# eMMC_FLASH.net
KiCad netlist of a schematic drawn in Altium Designer
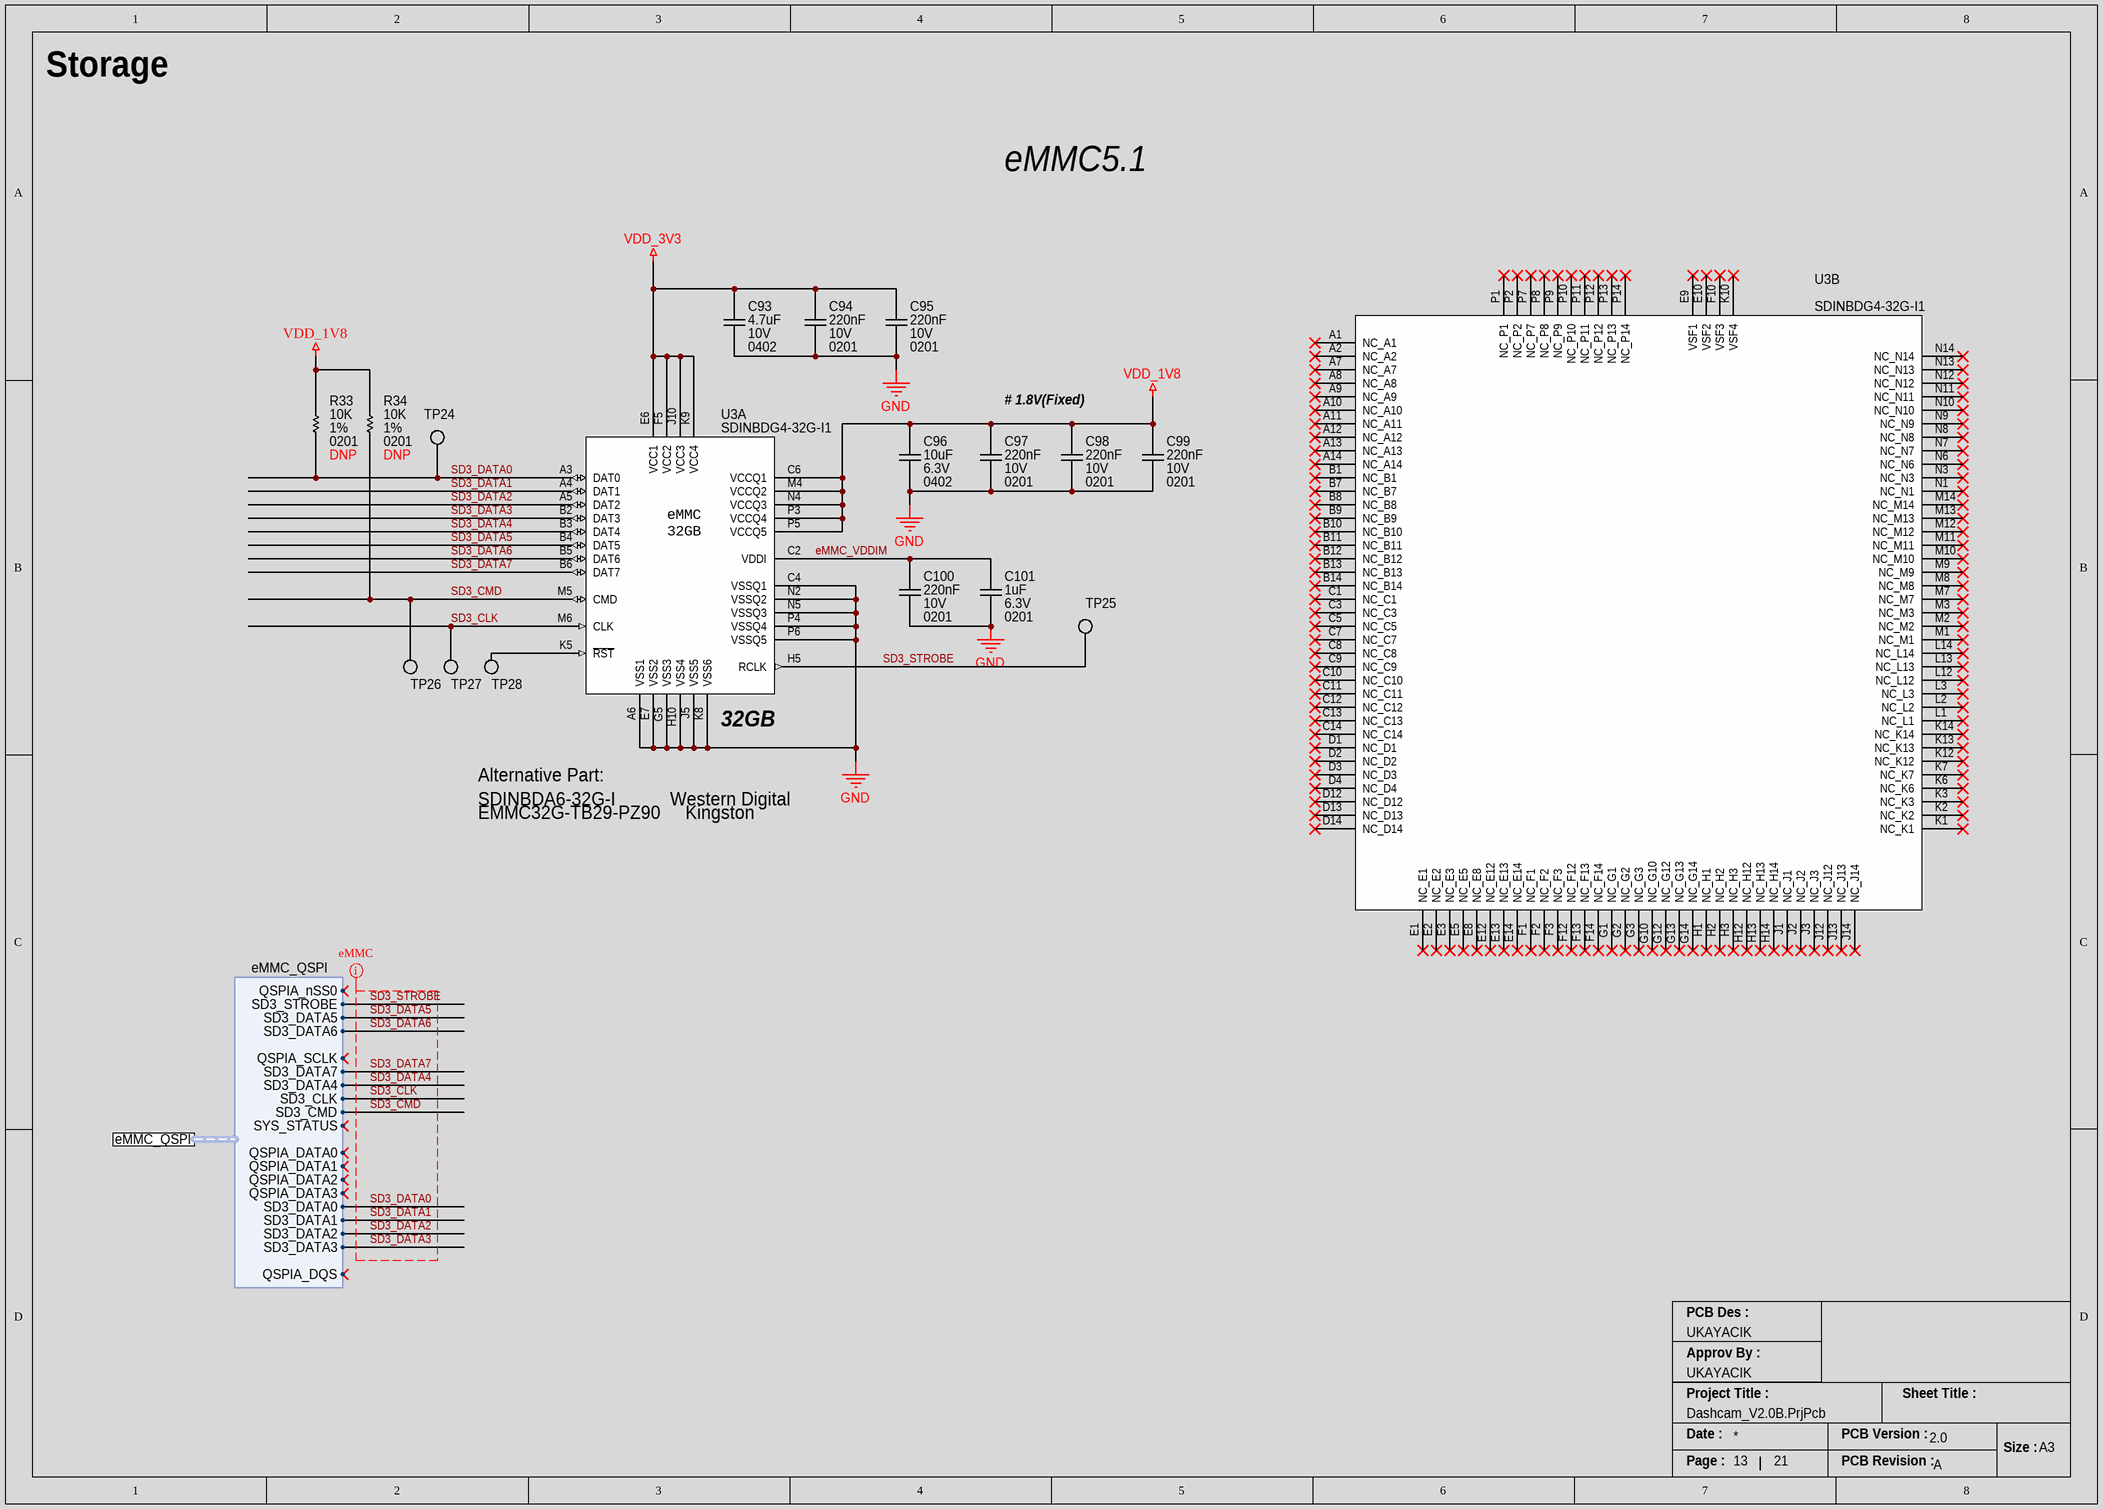
[diagram p0: eMMC FLASH.SchDoc]

(export (version "E")
  (design (tool "Eeschema 10.0.6"))
  (components
    (comp (ref "C93")
      (value "CL05A475KP5NRNC")
      (footprint "CAP_0402_CAPC1005X05N")
      (description "Multilayer Ceramic Capacitor, 4.7 uF, 10 V, ± 10%, X5R, 0402 [1005 Metric]")
      (fields
        (field (name "MANUFACTURER") "Samsung")
        (field (name "TOLERANCE") "10%")
        (field (name "CAPACITANCE") "4.7uF")
        (field (name "VOLTAGE RATING") "10V")
        (field (name "CASE/PACKAGE") "0402")
      )
      (libsource (lib "Electronic Devices_LIB") (part "CAP_4.7UF_10V_X5R_0402"))
    )
    (comp (ref "C94")
      (value "LMK063BJ224MP-F")
      (footprint "CAP_0201_CAPC0603X03N")
      (description "Multilayer Ceramic Capacitors (High dielectric type), 10V, 0.22 uF, ± 20 %, 0201, X5R, RoHS")
      (fields
        (field (name "MANUFACTURER") "Taiyo Yuden")
        (field (name "TOLERANCE") "20%")
        (field (name "VOLTAGE RATING (DC)") "10V")
        (field (name "CAPACITANCE") "220nF")
        (field (name "CASE/PACKAGE") "0201")
      )
      (libsource (lib "Electronic Devices_LIB") (part "CAP_0.22UF_10V_X5R_0201"))
    )
    (comp (ref "C95")
      (value "LMK063BJ224MP-F")
      (footprint "CAP_0201_CAPC0603X03N")
      (description "Multilayer Ceramic Capacitors (High dielectric type), 10V, 0.22 uF, ± 20 %, 0201, X5R, RoHS")
      (fields
        (field (name "MANUFACTURER") "Taiyo Yuden")
        (field (name "TOLERANCE") "20%")
        (field (name "VOLTAGE RATING (DC)") "10V")
        (field (name "CAPACITANCE") "220nF")
        (field (name "CASE/PACKAGE") "0201")
      )
      (libsource (lib "Electronic Devices_LIB") (part "CAP_0.22UF_10V_X5R_0201"))
    )
    (comp (ref "C96")
      (value "CL05A106MQ5NUNC")
      (footprint "CAP_0402_CAPC1005X05N")
      (description "Cap Ceramic 10uF 6.3V X5R 20% SMD 0402 85C T/R")
      (fields
        (field (name "MANUFACTURER") "Samsung")
        (field (name "TOLERANCE") "20%")
        (field (name "CASE/PACKAGE") "0402")
        (field (name "CAPACITANCE") "10uF")
        (field (name "VOLTAGE RATING") "6.3V")
      )
      (libsource (lib "Electronic Devices_LIB") (part "CAP_10UF_6.3V_X5R_0402"))
    )
    (comp (ref "C97")
      (value "LMK063BJ224MP-F")
      (footprint "CAP_0201_CAPC0603X03N")
      (description "Multilayer Ceramic Capacitors (High dielectric type), 10V, 0.22 uF, ± 20 %, 0201, X5R, RoHS")
      (fields
        (field (name "MANUFACTURER") "Taiyo Yuden")
        (field (name "TOLERANCE") "20%")
        (field (name "VOLTAGE RATING (DC)") "10V")
        (field (name "CAPACITANCE") "220nF")
        (field (name "CASE/PACKAGE") "0201")
      )
      (libsource (lib "Electronic Devices_LIB") (part "CAP_0.22UF_10V_X5R_0201"))
    )
    (comp (ref "C98")
      (value "LMK063BJ224MP-F")
      (footprint "CAP_0201_CAPC0603X03N")
      (description "Multilayer Ceramic Capacitors (High dielectric type), 10V, 0.22 uF, ± 20 %, 0201, X5R, RoHS")
      (fields
        (field (name "MANUFACTURER") "Taiyo Yuden")
        (field (name "TOLERANCE") "20%")
        (field (name "VOLTAGE RATING (DC)") "10V")
        (field (name "CAPACITANCE") "220nF")
        (field (name "CASE/PACKAGE") "0201")
      )
      (libsource (lib "Electronic Devices_LIB") (part "CAP_0.22UF_10V_X5R_0201"))
    )
    (comp (ref "C99")
      (value "LMK063BJ224MP-F")
      (footprint "CAP_0201_CAPC0603X03N")
      (description "Multilayer Ceramic Capacitors (High dielectric type), 10V, 0.22 uF, ± 20 %, 0201, X5R, RoHS")
      (fields
        (field (name "MANUFACTURER") "Taiyo Yuden")
        (field (name "TOLERANCE") "20%")
        (field (name "VOLTAGE RATING (DC)") "10V")
        (field (name "CAPACITANCE") "220nF")
        (field (name "CASE/PACKAGE") "0201")
      )
      (libsource (lib "Electronic Devices_LIB") (part "CAP_0.22UF_10V_X5R_0201"))
    )
    (comp (ref "C100")
      (value "LMK063BJ224MP-F")
      (footprint "CAP_0201_CAPC0603X03N")
      (description "Multilayer Ceramic Capacitors (High dielectric type), 10V, 0.22 uF, ± 20 %, 0201, X5R, RoHS")
      (fields
        (field (name "MANUFACTURER") "Taiyo Yuden")
        (field (name "TOLERANCE") "20%")
        (field (name "VOLTAGE RATING (DC)") "10V")
        (field (name "CAPACITANCE") "220nF")
        (field (name "CASE/PACKAGE") "0201")
      )
      (libsource (lib "Electronic Devices_LIB") (part "CAP_0.22UF_10V_X5R_0201"))
    )
    (comp (ref "C101")
      (value "02016D105MAT2A")
      (footprint "CAP_0201_CAPC0603X03N")
      (description "0201 1 uF 6.3 V ±20 % Tolerance X5R Surface Mount Multilayer Ceramic Capacitor")
      (fields
        (field (name "MANUFACTURER") "Kyocera AVX")
        (field (name "TOLERANCE") "20%")
        (field (name "VOLTAGE RATING (DC)") "6.3V")
        (field (name "CAPACITANCE") "1uF")
        (field (name "CASE/PACKAGE") "0201")
      )
      (libsource (lib "Electronic Devices_LIB") (part "CAP_1UF_6.3V_X5R_0201"))
    )
    (comp (ref "R33")
      (value "RC0201FR-0710KL")
      (footprint "RES_0201_RESC0603X02N")
      (description "SMD Chip Resistor, 10 kOhm, ± 1%, 50 mW, 0201 [0603 Metric], Thick Film, General Purpose")
      (fields
        (field (name "MANUFACTURER") "Yageo")
        (field (name "TOLERANCE") "1%")
        (field (name "RESISTANCE") "10K")
        (field (name "CASE CODE (IMPERIAL)") "0201")
      )
      (libsource (lib "Electronic Devices_LIB") (part "RES_10K_1/12W_1%_0201"))
    )
    (comp (ref "R34")
      (value "RC0201FR-0710KL")
      (footprint "RES_0201_RESC0603X02N")
      (description "SMD Chip Resistor, 10 kOhm, ± 1%, 50 mW, 0201 [0603 Metric], Thick Film, General Purpose")
      (fields
        (field (name "MANUFACTURER") "Yageo")
        (field (name "TOLERANCE") "1%")
        (field (name "RESISTANCE") "10K")
        (field (name "CASE CODE (IMPERIAL)") "0201")
      )
      (libsource (lib "Electronic Devices_LIB") (part "RES_10K_1/12W_1%_0201"))
    )
    (comp (ref "TP24")
      (value "NO COMPONENT")
      (footprint "TP_PAD_0.5MM_SMD_ROUND")
      (description "Test Point, SMD pad, round, 1.5mm, 1.6mm, 3mm diameter")
      (libsource (lib "Electronic Devices_LIB") (part "TP_PAD_SMD_SMALL"))
    )
    (comp (ref "TP25")
      (value "NO COMPONENT")
      (footprint "TP_PAD_0.5MM_SMD_ROUND")
      (description "Test Point, SMD pad, round, 1.5mm, 1.6mm, 3mm diameter")
      (libsource (lib "Electronic Devices_LIB") (part "TP_PAD_SMD_SMALL"))
    )
    (comp (ref "TP26")
      (value "NO COMPONENT")
      (footprint "TP_PAD_0.5MM_SMD_ROUND")
      (description "Test Point, SMD pad, round, 1.5mm, 1.6mm, 3mm diameter")
      (libsource (lib "Electronic Devices_LIB") (part "TP_PAD_SMD_SMALL"))
    )
    (comp (ref "TP27")
      (value "NO COMPONENT")
      (footprint "TP_PAD_0.5MM_SMD_ROUND")
      (description "Test Point, SMD pad, round, 1.5mm, 1.6mm, 3mm diameter")
      (libsource (lib "Electronic Devices_LIB") (part "TP_PAD_SMD_SMALL"))
    )
    (comp (ref "TP28")
      (value "NO COMPONENT")
      (footprint "TP_PAD_0.5MM_SMD_ROUND")
      (description "Test Point, SMD pad, round, 1.5mm, 1.6mm, 3mm diameter")
      (libsource (lib "Electronic Devices_LIB") (part "TP_PAD_SMD_SMALL"))
    )
    (comp (ref "U3")
      (value "SDINBDG4-32G-I1")
      (footprint "IC_MEMORY_eMMC")
      (description "Inand 7250 32GB Industrial Wide Temp -25C+85C EMMC5.1 HS400")
      (fields (field (name "MANUFACTURER") "SanDisk"))
      (libsource (lib "Electronic Devices_LIB") (part "IC_MEMORY_eMMC_SDINBDG4-32G-I1"))
    )
  )
  (nets
    (net (code "2") (name "/SD3_CLK") (class "Default")
      (node (ref "TP27") (pin "1") (pinfunction "1_1") (pintype "passive"))
      (node (ref "U3") (pin "M6") (pinfunction "CLK_M6") (pintype "input"))
    )
    (net (code "3") (name "/SD3_CMD") (class "Default")
      (node (ref "R34") (pin "1") (pinfunction "1_1") (pintype "passive"))
      (node (ref "TP26") (pin "1") (pinfunction "1_1") (pintype "passive"))
      (node (ref "U3") (pin "M5") (pinfunction "CMD_M5") (pintype "bidirectional"))
    )
    (net (code "4") (name "/SD3_DATA0") (class "Default")
      (node (ref "R33") (pin "1") (pinfunction "1_1") (pintype "passive"))
      (node (ref "TP24") (pin "1") (pinfunction "1_1") (pintype "passive"))
      (node (ref "U3") (pin "A3") (pinfunction "DAT0_A3") (pintype "bidirectional"))
    )
    (net (code "5") (name "/SD3_DATA1") (class "Default")
      (node (ref "U3") (pin "A4") (pinfunction "DAT1_A4") (pintype "bidirectional"))
    )
    (net (code "6") (name "/SD3_DATA2") (class "Default")
      (node (ref "U3") (pin "A5") (pinfunction "DAT2_A5") (pintype "bidirectional"))
    )
    (net (code "7") (name "/SD3_DATA3") (class "Default")
      (node (ref "U3") (pin "B2") (pinfunction "DAT3_B2") (pintype "bidirectional"))
    )
    (net (code "8") (name "/SD3_DATA4") (class "Default")
      (node (ref "U3") (pin "B3") (pinfunction "DAT4_B3") (pintype "bidirectional"))
    )
    (net (code "9") (name "/SD3_DATA5") (class "Default")
      (node (ref "U3") (pin "B4") (pinfunction "DAT5_B4") (pintype "bidirectional"))
    )
    (net (code "10") (name "/SD3_DATA6") (class "Default")
      (node (ref "U3") (pin "B5") (pinfunction "DAT6_B5") (pintype "bidirectional"))
    )
    (net (code "11") (name "/SD3_DATA7") (class "Default")
      (node (ref "U3") (pin "B6") (pinfunction "DAT7_B6") (pintype "bidirectional"))
    )
    (net (code "12") (name "/SD3_STROBE") (class "Default")
      (node (ref "TP25") (pin "1") (pinfunction "1_1") (pintype "passive"))
      (node (ref "U3") (pin "H5") (pinfunction "RCLK_H5") (pintype "output"))
    )
    (net (code "13") (name "/eMMC_VDDIM") (class "Default")
      (node (ref "C100") (pin "2") (pinfunction "2_2") (pintype "passive"))
      (node (ref "C101") (pin "2") (pinfunction "2_2") (pintype "passive"))
      (node (ref "U3") (pin "C2") (pinfunction "VDDI_C2") (pintype "power_in"))
    )
    (net (code "15") (name "GND") (class "Default")
      (node (ref "C100") (pin "1") (pinfunction "1_1") (pintype "passive"))
      (node (ref "C101") (pin "1") (pinfunction "1_1") (pintype "passive"))
      (node (ref "C93") (pin "1") (pinfunction "1_1") (pintype "passive"))
      (node (ref "C94") (pin "1") (pinfunction "1_1") (pintype "passive"))
      (node (ref "C95") (pin "1") (pinfunction "1_1") (pintype "passive"))
      (node (ref "C96") (pin "1") (pinfunction "1_1") (pintype "passive"))
      (node (ref "C97") (pin "1") (pinfunction "1_1") (pintype "passive"))
      (node (ref "C98") (pin "1") (pinfunction "1_1") (pintype "passive"))
      (node (ref "C99") (pin "1") (pinfunction "1_1") (pintype "passive"))
      (node (ref "U3") (pin "A6") (pinfunction "VSS1_A6") (pintype "power_in"))
      (node (ref "U3") (pin "C4") (pinfunction "VSSQ1_C4") (pintype "power_in"))
      (node (ref "U3") (pin "E7") (pinfunction "VSS2_E7") (pintype "power_in"))
      (node (ref "U3") (pin "G5") (pinfunction "VSS3_G5") (pintype "power_in"))
      (node (ref "U3") (pin "H10") (pinfunction "VSS4_H10") (pintype "power_in"))
      (node (ref "U3") (pin "J5") (pinfunction "VSS5_J5") (pintype "power_in"))
      (node (ref "U3") (pin "K8") (pinfunction "VSS6_K8") (pintype "power_in"))
      (node (ref "U3") (pin "N2") (pinfunction "VSSQ2_N2") (pintype "power_in"))
      (node (ref "U3") (pin "N5") (pinfunction "VSSQ3_N5") (pintype "power_in"))
      (node (ref "U3") (pin "P4") (pinfunction "VSSQ4_P4") (pintype "power_in"))
      (node (ref "U3") (pin "P6") (pinfunction "VSSQ5_P6") (pintype "power_in"))
    )
    (net (code "16") (name "Net-(U3A-~{RST})") (class "Default")
      (node (ref "TP28") (pin "1") (pinfunction "1_1") (pintype "passive"))
      (node (ref "U3") (pin "K5") (pinfunction "~{RST}_K5") (pintype "input"))
    )
    (net (code "17") (name "VDD_1V8") (class "Default")
      (node (ref "C96") (pin "2") (pinfunction "2_2") (pintype "passive"))
      (node (ref "C97") (pin "2") (pinfunction "2_2") (pintype "passive"))
      (node (ref "C98") (pin "2") (pinfunction "2_2") (pintype "passive"))
      (node (ref "C99") (pin "2") (pinfunction "2_2") (pintype "passive"))
      (node (ref "R33") (pin "2") (pinfunction "2_2") (pintype "passive"))
      (node (ref "R34") (pin "2") (pinfunction "2_2") (pintype "passive"))
      (node (ref "U3") (pin "C6") (pinfunction "VCCQ1_C6") (pintype "power_in"))
      (node (ref "U3") (pin "M4") (pinfunction "VCCQ2_M4") (pintype "power_in"))
      (node (ref "U3") (pin "N4") (pinfunction "VCCQ3_N4") (pintype "power_in"))
      (node (ref "U3") (pin "P3") (pinfunction "VCCQ4_P3") (pintype "power_in"))
      (node (ref "U3") (pin "P5") (pinfunction "VCCQ5_P5") (pintype "power_in"))
    )
    (net (code "18") (name "VDD_3V3") (class "Default")
      (node (ref "C93") (pin "2") (pinfunction "2_2") (pintype "passive"))
      (node (ref "C94") (pin "2") (pinfunction "2_2") (pintype "passive"))
      (node (ref "C95") (pin "2") (pinfunction "2_2") (pintype "passive"))
      (node (ref "U3") (pin "E6") (pinfunction "VCC1_E6") (pintype "power_in"))
      (node (ref "U3") (pin "F5") (pinfunction "VCC2_F5") (pintype "power_in"))
      (node (ref "U3") (pin "J10") (pinfunction "VCC3_J10") (pintype "power_in"))
      (node (ref "U3") (pin "K9") (pinfunction "VCC4_K9") (pintype "power_in"))
    )
    (net (code "19") (name "unconnected-(U3B-NC_A1-PadA1)") (class "Default")
      (node (ref "U3") (pin "A1") (pinfunction "NC_A1_A1") (pintype "passive+no_connect"))
    )
    (net (code "20") (name "unconnected-(U3B-NC_A2-PadA2)") (class "Default")
      (node (ref "U3") (pin "A2") (pinfunction "NC_A2_A2") (pintype "passive+no_connect"))
    )
    (net (code "21") (name "unconnected-(U3B-NC_A7-PadA7)") (class "Default")
      (node (ref "U3") (pin "A7") (pinfunction "NC_A7_A7") (pintype "passive+no_connect"))
    )
    (net (code "22") (name "unconnected-(U3B-NC_A8-PadA8)") (class "Default")
      (node (ref "U3") (pin "A8") (pinfunction "NC_A8_A8") (pintype "passive+no_connect"))
    )
    (net (code "23") (name "unconnected-(U3B-NC_A9-PadA9)") (class "Default")
      (node (ref "U3") (pin "A9") (pinfunction "NC_A9_A9") (pintype "passive+no_connect"))
    )
    (net (code "24") (name "unconnected-(U3B-NC_A10-PadA10)") (class "Default")
      (node (ref "U3") (pin "A10") (pinfunction "NC_A10_A10") (pintype "passive+no_connect"))
    )
    (net (code "25") (name "unconnected-(U3B-NC_A11-PadA11)") (class "Default")
      (node (ref "U3") (pin "A11") (pinfunction "NC_A11_A11") (pintype "passive+no_connect"))
    )
    (net (code "26") (name "unconnected-(U3B-NC_A12-PadA12)") (class "Default")
      (node (ref "U3") (pin "A12") (pinfunction "NC_A12_A12") (pintype "passive+no_connect"))
    )
    (net (code "27") (name "unconnected-(U3B-NC_A13-PadA13)") (class "Default")
      (node (ref "U3") (pin "A13") (pinfunction "NC_A13_A13") (pintype "passive+no_connect"))
    )
    (net (code "28") (name "unconnected-(U3B-NC_A14-PadA14)") (class "Default")
      (node (ref "U3") (pin "A14") (pinfunction "NC_A14_A14") (pintype "passive+no_connect"))
    )
    (net (code "29") (name "unconnected-(U3B-NC_B1-PadB1)") (class "Default")
      (node (ref "U3") (pin "B1") (pinfunction "NC_B1_B1") (pintype "passive+no_connect"))
    )
    (net (code "30") (name "unconnected-(U3B-NC_B7-PadB7)") (class "Default")
      (node (ref "U3") (pin "B7") (pinfunction "NC_B7_B7") (pintype "passive+no_connect"))
    )
    (net (code "31") (name "unconnected-(U3B-NC_B8-PadB8)") (class "Default")
      (node (ref "U3") (pin "B8") (pinfunction "NC_B8_B8") (pintype "passive+no_connect"))
    )
    (net (code "32") (name "unconnected-(U3B-NC_B9-PadB9)") (class "Default")
      (node (ref "U3") (pin "B9") (pinfunction "NC_B9_B9") (pintype "passive+no_connect"))
    )
    (net (code "33") (name "unconnected-(U3B-NC_B10-PadB10)") (class "Default")
      (node (ref "U3") (pin "B10") (pinfunction "NC_B10_B10") (pintype "passive+no_connect"))
    )
    (net (code "34") (name "unconnected-(U3B-NC_B11-PadB11)") (class "Default")
      (node (ref "U3") (pin "B11") (pinfunction "NC_B11_B11") (pintype "passive+no_connect"))
    )
    (net (code "35") (name "unconnected-(U3B-NC_B12-PadB12)") (class "Default")
      (node (ref "U3") (pin "B12") (pinfunction "NC_B12_B12") (pintype "passive+no_connect"))
    )
    (net (code "36") (name "unconnected-(U3B-NC_B13-PadB13)") (class "Default")
      (node (ref "U3") (pin "B13") (pinfunction "NC_B13_B13") (pintype "passive+no_connect"))
    )
    (net (code "37") (name "unconnected-(U3B-NC_B14-PadB14)") (class "Default")
      (node (ref "U3") (pin "B14") (pinfunction "NC_B14_B14") (pintype "passive+no_connect"))
    )
    (net (code "38") (name "unconnected-(U3B-NC_C1-PadC1)") (class "Default")
      (node (ref "U3") (pin "C1") (pinfunction "NC_C1_C1") (pintype "passive+no_connect"))
    )
    (net (code "39") (name "unconnected-(U3B-NC_C3-PadC3)") (class "Default")
      (node (ref "U3") (pin "C3") (pinfunction "NC_C3_C3") (pintype "passive+no_connect"))
    )
    (net (code "40") (name "unconnected-(U3B-NC_C5-PadC5)") (class "Default")
      (node (ref "U3") (pin "C5") (pinfunction "NC_C5_C5") (pintype "passive+no_connect"))
    )
    (net (code "41") (name "unconnected-(U3B-NC_C7-PadC7)") (class "Default")
      (node (ref "U3") (pin "C7") (pinfunction "NC_C7_C7") (pintype "passive+no_connect"))
    )
    (net (code "42") (name "unconnected-(U3B-NC_C8-PadC8)") (class "Default")
      (node (ref "U3") (pin "C8") (pinfunction "NC_C8_C8") (pintype "passive+no_connect"))
    )
    (net (code "43") (name "unconnected-(U3B-NC_C9-PadC9)") (class "Default")
      (node (ref "U3") (pin "C9") (pinfunction "NC_C9_C9") (pintype "passive+no_connect"))
    )
    (net (code "44") (name "unconnected-(U3B-NC_C10-PadC10)") (class "Default")
      (node (ref "U3") (pin "C10") (pinfunction "NC_C10_C10") (pintype "passive+no_connect"))
    )
    (net (code "45") (name "unconnected-(U3B-NC_C11-PadC11)") (class "Default")
      (node (ref "U3") (pin "C11") (pinfunction "NC_C11_C11") (pintype "passive+no_connect"))
    )
    (net (code "46") (name "unconnected-(U3B-NC_C12-PadC12)") (class "Default")
      (node (ref "U3") (pin "C12") (pinfunction "NC_C12_C12") (pintype "passive+no_connect"))
    )
    (net (code "47") (name "unconnected-(U3B-NC_C13-PadC13)") (class "Default")
      (node (ref "U3") (pin "C13") (pinfunction "NC_C13_C13") (pintype "passive+no_connect"))
    )
    (net (code "48") (name "unconnected-(U3B-NC_C14-PadC14)") (class "Default")
      (node (ref "U3") (pin "C14") (pinfunction "NC_C14_C14") (pintype "passive+no_connect"))
    )
    (net (code "49") (name "unconnected-(U3B-NC_D1-PadD1)") (class "Default")
      (node (ref "U3") (pin "D1") (pinfunction "NC_D1_D1") (pintype "passive+no_connect"))
    )
    (net (code "50") (name "unconnected-(U3B-NC_D2-PadD2)") (class "Default")
      (node (ref "U3") (pin "D2") (pinfunction "NC_D2_D2") (pintype "passive+no_connect"))
    )
    (net (code "51") (name "unconnected-(U3B-NC_D3-PadD3)") (class "Default")
      (node (ref "U3") (pin "D3") (pinfunction "NC_D3_D3") (pintype "passive+no_connect"))
    )
    (net (code "52") (name "unconnected-(U3B-NC_D4-PadD4)") (class "Default")
      (node (ref "U3") (pin "D4") (pinfunction "NC_D4_D4") (pintype "passive+no_connect"))
    )
    (net (code "53") (name "unconnected-(U3B-NC_D12-PadD12)") (class "Default")
      (node (ref "U3") (pin "D12") (pinfunction "NC_D12_D12") (pintype "passive+no_connect"))
    )
    (net (code "54") (name "unconnected-(U3B-NC_D13-PadD13)") (class "Default")
      (node (ref "U3") (pin "D13") (pinfunction "NC_D13_D13") (pintype "passive+no_connect"))
    )
    (net (code "55") (name "unconnected-(U3B-NC_D14-PadD14)") (class "Default")
      (node (ref "U3") (pin "D14") (pinfunction "NC_D14_D14") (pintype "passive+no_connect"))
    )
    (net (code "56") (name "unconnected-(U3B-NC_E1-PadE1)") (class "Default")
      (node (ref "U3") (pin "E1") (pinfunction "NC_E1_E1") (pintype "passive+no_connect"))
    )
    (net (code "57") (name "unconnected-(U3B-NC_E2-PadE2)") (class "Default")
      (node (ref "U3") (pin "E2") (pinfunction "NC_E2_E2") (pintype "passive+no_connect"))
    )
    (net (code "58") (name "unconnected-(U3B-NC_E3-PadE3)") (class "Default")
      (node (ref "U3") (pin "E3") (pinfunction "NC_E3_E3") (pintype "passive+no_connect"))
    )
    (net (code "59") (name "unconnected-(U3B-NC_E5-PadE5)") (class "Default")
      (node (ref "U3") (pin "E5") (pinfunction "NC_E5_E5") (pintype "passive+no_connect"))
    )
    (net (code "60") (name "unconnected-(U3B-NC_E8-PadE8)") (class "Default")
      (node (ref "U3") (pin "E8") (pinfunction "NC_E8_E8") (pintype "passive+no_connect"))
    )
    (net (code "61") (name "unconnected-(U3B-NC_E12-PadE12)") (class "Default")
      (node (ref "U3") (pin "E12") (pinfunction "NC_E12_E12") (pintype "passive+no_connect"))
    )
    (net (code "62") (name "unconnected-(U3B-NC_E13-PadE13)") (class "Default")
      (node (ref "U3") (pin "E13") (pinfunction "NC_E13_E13") (pintype "passive+no_connect"))
    )
    (net (code "63") (name "unconnected-(U3B-NC_E14-PadE14)") (class "Default")
      (node (ref "U3") (pin "E14") (pinfunction "NC_E14_E14") (pintype "passive+no_connect"))
    )
    (net (code "64") (name "unconnected-(U3B-NC_F1-PadF1)") (class "Default")
      (node (ref "U3") (pin "F1") (pinfunction "NC_F1_F1") (pintype "passive+no_connect"))
    )
    (net (code "65") (name "unconnected-(U3B-NC_F2-PadF2)") (class "Default")
      (node (ref "U3") (pin "F2") (pinfunction "NC_F2_F2") (pintype "passive+no_connect"))
    )
    (net (code "66") (name "unconnected-(U3B-NC_F3-PadF3)") (class "Default")
      (node (ref "U3") (pin "F3") (pinfunction "NC_F3_F3") (pintype "passive+no_connect"))
    )
    (net (code "67") (name "unconnected-(U3B-NC_F12-PadF12)") (class "Default")
      (node (ref "U3") (pin "F12") (pinfunction "NC_F12_F12") (pintype "passive+no_connect"))
    )
    (net (code "68") (name "unconnected-(U3B-NC_F13-PadF13)") (class "Default")
      (node (ref "U3") (pin "F13") (pinfunction "NC_F13_F13") (pintype "passive+no_connect"))
    )
    (net (code "69") (name "unconnected-(U3B-NC_F14-PadF14)") (class "Default")
      (node (ref "U3") (pin "F14") (pinfunction "NC_F14_F14") (pintype "passive+no_connect"))
    )
    (net (code "70") (name "unconnected-(U3B-NC_G1-PadG1)") (class "Default")
      (node (ref "U3") (pin "G1") (pinfunction "NC_G1_G1") (pintype "passive+no_connect"))
    )
    (net (code "71") (name "unconnected-(U3B-NC_G2-PadG2)") (class "Default")
      (node (ref "U3") (pin "G2") (pinfunction "NC_G2_G2") (pintype "passive+no_connect"))
    )
    (net (code "72") (name "unconnected-(U3B-NC_G3-PadG3)") (class "Default")
      (node (ref "U3") (pin "G3") (pinfunction "NC_G3_G3") (pintype "passive+no_connect"))
    )
    (net (code "73") (name "unconnected-(U3B-NC_G10-PadG10)") (class "Default")
      (node (ref "U3") (pin "G10") (pinfunction "NC_G10_G10") (pintype "passive+no_connect"))
    )
    (net (code "74") (name "unconnected-(U3B-NC_G12-PadG12)") (class "Default")
      (node (ref "U3") (pin "G12") (pinfunction "NC_G12_G12") (pintype "passive+no_connect"))
    )
    (net (code "75") (name "unconnected-(U3B-NC_G13-PadG13)") (class "Default")
      (node (ref "U3") (pin "G13") (pinfunction "NC_G13_G13") (pintype "passive+no_connect"))
    )
    (net (code "76") (name "unconnected-(U3B-NC_G14-PadG14)") (class "Default")
      (node (ref "U3") (pin "G14") (pinfunction "NC_G14_G14") (pintype "passive+no_connect"))
    )
    (net (code "77") (name "unconnected-(U3B-NC_H1-PadH1)") (class "Default")
      (node (ref "U3") (pin "H1") (pinfunction "NC_H1_H1") (pintype "passive+no_connect"))
    )
    (net (code "78") (name "unconnected-(U3B-NC_H2-PadH2)") (class "Default")
      (node (ref "U3") (pin "H2") (pinfunction "NC_H2_H2") (pintype "passive+no_connect"))
    )
    (net (code "79") (name "unconnected-(U3B-NC_H3-PadH3)") (class "Default")
      (node (ref "U3") (pin "H3") (pinfunction "NC_H3_H3") (pintype "passive+no_connect"))
    )
    (net (code "80") (name "unconnected-(U3B-NC_H12-PadH12)") (class "Default")
      (node (ref "U3") (pin "H12") (pinfunction "NC_H12_H12") (pintype "passive+no_connect"))
    )
    (net (code "81") (name "unconnected-(U3B-NC_H13-PadH13)") (class "Default")
      (node (ref "U3") (pin "H13") (pinfunction "NC_H13_H13") (pintype "passive+no_connect"))
    )
    (net (code "82") (name "unconnected-(U3B-NC_H14-PadH14)") (class "Default")
      (node (ref "U3") (pin "H14") (pinfunction "NC_H14_H14") (pintype "passive+no_connect"))
    )
    (net (code "83") (name "unconnected-(U3B-NC_J1-PadJ1)") (class "Default")
      (node (ref "U3") (pin "J1") (pinfunction "NC_J1_J1") (pintype "passive+no_connect"))
    )
    (net (code "84") (name "unconnected-(U3B-NC_J2-PadJ2)") (class "Default")
      (node (ref "U3") (pin "J2") (pinfunction "NC_J2_J2") (pintype "passive+no_connect"))
    )
    (net (code "85") (name "unconnected-(U3B-NC_J3-PadJ3)") (class "Default")
      (node (ref "U3") (pin "J3") (pinfunction "NC_J3_J3") (pintype "passive+no_connect"))
    )
    (net (code "86") (name "unconnected-(U3B-NC_J12-PadJ12)") (class "Default")
      (node (ref "U3") (pin "J12") (pinfunction "NC_J12_J12") (pintype "passive+no_connect"))
    )
    (net (code "87") (name "unconnected-(U3B-NC_J13-PadJ13)") (class "Default")
      (node (ref "U3") (pin "J13") (pinfunction "NC_J13_J13") (pintype "passive+no_connect"))
    )
    (net (code "88") (name "unconnected-(U3B-NC_J14-PadJ14)") (class "Default")
      (node (ref "U3") (pin "J14") (pinfunction "NC_J14_J14") (pintype "passive+no_connect"))
    )
    (net (code "89") (name "unconnected-(U3B-NC_K1-PadK1)") (class "Default")
      (node (ref "U3") (pin "K1") (pinfunction "NC_K1_K1") (pintype "passive+no_connect"))
    )
    (net (code "90") (name "unconnected-(U3B-NC_K2-PadK2)") (class "Default")
      (node (ref "U3") (pin "K2") (pinfunction "NC_K2_K2") (pintype "passive+no_connect"))
    )
    (net (code "91") (name "unconnected-(U3B-NC_K3-PadK3)") (class "Default")
      (node (ref "U3") (pin "K3") (pinfunction "NC_K3_K3") (pintype "passive+no_connect"))
    )
    (net (code "92") (name "unconnected-(U3B-NC_K6-PadK6)") (class "Default")
      (node (ref "U3") (pin "K6") (pinfunction "NC_K6_K6") (pintype "passive+no_connect"))
    )
    (net (code "93") (name "unconnected-(U3B-NC_K7-PadK7)") (class "Default")
      (node (ref "U3") (pin "K7") (pinfunction "NC_K7_K7") (pintype "passive+no_connect"))
    )
    (net (code "94") (name "unconnected-(U3B-NC_K12-PadK12)") (class "Default")
      (node (ref "U3") (pin "K12") (pinfunction "NC_K12_K12") (pintype "passive+no_connect"))
    )
    (net (code "95") (name "unconnected-(U3B-NC_K13-PadK13)") (class "Default")
      (node (ref "U3") (pin "K13") (pinfunction "NC_K13_K13") (pintype "passive+no_connect"))
    )
    (net (code "96") (name "unconnected-(U3B-NC_K14-PadK14)") (class "Default")
      (node (ref "U3") (pin "K14") (pinfunction "NC_K14_K14") (pintype "passive+no_connect"))
    )
    (net (code "97") (name "unconnected-(U3B-NC_L1-PadL1)") (class "Default")
      (node (ref "U3") (pin "L1") (pinfunction "NC_L1_L1") (pintype "passive+no_connect"))
    )
    (net (code "98") (name "unconnected-(U3B-NC_L2-PadL2)") (class "Default")
      (node (ref "U3") (pin "L2") (pinfunction "NC_L2_L2") (pintype "passive+no_connect"))
    )
    (net (code "99") (name "unconnected-(U3B-NC_L3-PadL3)") (class "Default")
      (node (ref "U3") (pin "L3") (pinfunction "NC_L3_L3") (pintype "passive+no_connect"))
    )
    (net (code "100") (name "unconnected-(U3B-NC_L12-PadL12)") (class "Default")
      (node (ref "U3") (pin "L12") (pinfunction "NC_L12_L12") (pintype "passive+no_connect"))
    )
    (net (code "101") (name "unconnected-(U3B-NC_L13-PadL13)") (class "Default")
      (node (ref "U3") (pin "L13") (pinfunction "NC_L13_L13") (pintype "passive+no_connect"))
    )
    (net (code "102") (name "unconnected-(U3B-NC_L14-PadL14)") (class "Default")
      (node (ref "U3") (pin "L14") (pinfunction "NC_L14_L14") (pintype "passive+no_connect"))
    )
    (net (code "103") (name "unconnected-(U3B-NC_M1-PadM1)") (class "Default")
      (node (ref "U3") (pin "M1") (pinfunction "NC_M1_M1") (pintype "passive+no_connect"))
    )
    (net (code "104") (name "unconnected-(U3B-NC_M2-PadM2)") (class "Default")
      (node (ref "U3") (pin "M2") (pinfunction "NC_M2_M2") (pintype "passive+no_connect"))
    )
    (net (code "105") (name "unconnected-(U3B-NC_M3-PadM3)") (class "Default")
      (node (ref "U3") (pin "M3") (pinfunction "NC_M3_M3") (pintype "passive+no_connect"))
    )
    (net (code "106") (name "unconnected-(U3B-NC_M7-PadM7)") (class "Default")
      (node (ref "U3") (pin "M7") (pinfunction "NC_M7_M7") (pintype "passive+no_connect"))
    )
    (net (code "107") (name "unconnected-(U3B-NC_M8-PadM8)") (class "Default")
      (node (ref "U3") (pin "M8") (pinfunction "NC_M8_M8") (pintype "passive+no_connect"))
    )
    (net (code "108") (name "unconnected-(U3B-NC_M9-PadM9)") (class "Default")
      (node (ref "U3") (pin "M9") (pinfunction "NC_M9_M9") (pintype "passive+no_connect"))
    )
    (net (code "109") (name "unconnected-(U3B-NC_M10-PadM10)") (class "Default")
      (node (ref "U3") (pin "M10") (pinfunction "NC_M10_M10") (pintype "passive+no_connect"))
    )
    (net (code "110") (name "unconnected-(U3B-NC_M11-PadM11)") (class "Default")
      (node (ref "U3") (pin "M11") (pinfunction "NC_M11_M11") (pintype "passive+no_connect"))
    )
    (net (code "111") (name "unconnected-(U3B-NC_M12-PadM12)") (class "Default")
      (node (ref "U3") (pin "M12") (pinfunction "NC_M12_M12") (pintype "passive+no_connect"))
    )
    (net (code "112") (name "unconnected-(U3B-NC_M13-PadM13)") (class "Default")
      (node (ref "U3") (pin "M13") (pinfunction "NC_M13_M13") (pintype "passive+no_connect"))
    )
    (net (code "113") (name "unconnected-(U3B-NC_M14-PadM14)") (class "Default")
      (node (ref "U3") (pin "M14") (pinfunction "NC_M14_M14") (pintype "passive+no_connect"))
    )
    (net (code "114") (name "unconnected-(U3B-NC_N1-PadN1)") (class "Default")
      (node (ref "U3") (pin "N1") (pinfunction "NC_N1_N1") (pintype "passive+no_connect"))
    )
    (net (code "115") (name "unconnected-(U3B-NC_N3-PadN3)") (class "Default")
      (node (ref "U3") (pin "N3") (pinfunction "NC_N3_N3") (pintype "passive+no_connect"))
    )
    (net (code "116") (name "unconnected-(U3B-NC_N6-PadN6)") (class "Default")
      (node (ref "U3") (pin "N6") (pinfunction "NC_N6_N6") (pintype "passive+no_connect"))
    )
    (net (code "117") (name "unconnected-(U3B-NC_N7-PadN7)") (class "Default")
      (node (ref "U3") (pin "N7") (pinfunction "NC_N7_N7") (pintype "passive+no_connect"))
    )
    (net (code "118") (name "unconnected-(U3B-NC_N8-PadN8)") (class "Default")
      (node (ref "U3") (pin "N8") (pinfunction "NC_N8_N8") (pintype "passive+no_connect"))
    )
    (net (code "119") (name "unconnected-(U3B-NC_N9-PadN9)") (class "Default")
      (node (ref "U3") (pin "N9") (pinfunction "NC_N9_N9") (pintype "passive+no_connect"))
    )
    (net (code "120") (name "unconnected-(U3B-NC_N10-PadN10)") (class "Default")
      (node (ref "U3") (pin "N10") (pinfunction "NC_N10_N10") (pintype "passive+no_connect"))
    )
    (net (code "121") (name "unconnected-(U3B-NC_N11-PadN11)") (class "Default")
      (node (ref "U3") (pin "N11") (pinfunction "NC_N11_N11") (pintype "passive+no_connect"))
    )
    (net (code "122") (name "unconnected-(U3B-NC_N12-PadN12)") (class "Default")
      (node (ref "U3") (pin "N12") (pinfunction "NC_N12_N12") (pintype "passive+no_connect"))
    )
    (net (code "123") (name "unconnected-(U3B-NC_N13-PadN13)") (class "Default")
      (node (ref "U3") (pin "N13") (pinfunction "NC_N13_N13") (pintype "passive+no_connect"))
    )
    (net (code "124") (name "unconnected-(U3B-NC_N14-PadN14)") (class "Default")
      (node (ref "U3") (pin "N14") (pinfunction "NC_N14_N14") (pintype "passive+no_connect"))
    )
    (net (code "125") (name "unconnected-(U3B-NC_P1-PadP1)") (class "Default")
      (node (ref "U3") (pin "P1") (pinfunction "NC_P1_P1") (pintype "passive+no_connect"))
    )
    (net (code "126") (name "unconnected-(U3B-NC_P2-PadP2)") (class "Default")
      (node (ref "U3") (pin "P2") (pinfunction "NC_P2_P2") (pintype "passive+no_connect"))
    )
    (net (code "127") (name "unconnected-(U3B-NC_P7-PadP7)") (class "Default")
      (node (ref "U3") (pin "P7") (pinfunction "NC_P7_P7") (pintype "passive+no_connect"))
    )
    (net (code "128") (name "unconnected-(U3B-NC_P8-PadP8)") (class "Default")
      (node (ref "U3") (pin "P8") (pinfunction "NC_P8_P8") (pintype "passive+no_connect"))
    )
    (net (code "129") (name "unconnected-(U3B-NC_P9-PadP9)") (class "Default")
      (node (ref "U3") (pin "P9") (pinfunction "NC_P9_P9") (pintype "passive+no_connect"))
    )
    (net (code "130") (name "unconnected-(U3B-NC_P10-PadP10)") (class "Default")
      (node (ref "U3") (pin "P10") (pinfunction "NC_P10_P10") (pintype "passive+no_connect"))
    )
    (net (code "131") (name "unconnected-(U3B-NC_P11-PadP11)") (class "Default")
      (node (ref "U3") (pin "P11") (pinfunction "NC_P11_P11") (pintype "passive+no_connect"))
    )
    (net (code "132") (name "unconnected-(U3B-NC_P12-PadP12)") (class "Default")
      (node (ref "U3") (pin "P12") (pinfunction "NC_P12_P12") (pintype "passive+no_connect"))
    )
    (net (code "133") (name "unconnected-(U3B-NC_P13-PadP13)") (class "Default")
      (node (ref "U3") (pin "P13") (pinfunction "NC_P13_P13") (pintype "passive+no_connect"))
    )
    (net (code "134") (name "unconnected-(U3B-NC_P14-PadP14)") (class "Default")
      (node (ref "U3") (pin "P14") (pinfunction "NC_P14_P14") (pintype "passive+no_connect"))
    )
    (net (code "135") (name "unconnected-(U3B-VSF1-PadE9)") (class "Default")
      (node (ref "U3") (pin "E9") (pinfunction "VSF1_E9") (pintype "passive+no_connect"))
    )
    (net (code "136") (name "unconnected-(U3B-VSF2-PadE10)") (class "Default")
      (node (ref "U3") (pin "E10") (pinfunction "VSF2_E10") (pintype "passive+no_connect"))
    )
    (net (code "137") (name "unconnected-(U3B-VSF3-PadF10)") (class "Default")
      (node (ref "U3") (pin "F10") (pinfunction "VSF3_F10") (pintype "passive+no_connect"))
    )
    (net (code "138") (name "unconnected-(U3B-VSF4-PadK10)") (class "Default")
      (node (ref "U3") (pin "K10") (pinfunction "VSF4_K10") (pintype "passive+no_connect"))
    )
  )
)
